# auto_resetter.net
KiCad netlist of a schematic drawn in EAGLE
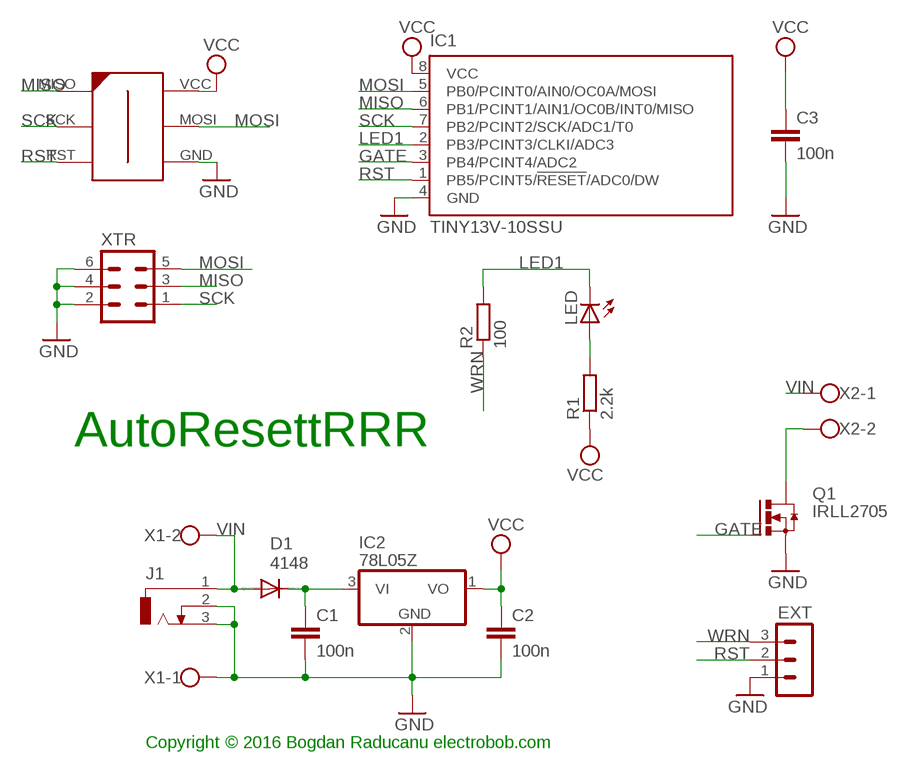
[diagram p0: schematic, sheet 1]

(export (version "E")
  (design (tool "Eeschema 10.0.6"))
  (components
    (comp (ref "C1")
      (value "100n")
      (footprint "eagle-import:C0805")
      (libsource (lib "eagle-import") (part "C-EUC0805"))
    )
    (comp (ref "C2")
      (value "100n")
      (footprint "eagle-import:C0805")
      (libsource (lib "eagle-import") (part "C-EUC0805"))
    )
    (comp (ref "C3")
      (value "100n")
      (footprint "eagle-import:C0805")
      (libsource (lib "eagle-import") (part "C-EUC0805"))
    )
    (comp (ref "D1")
      (value "4148")
      (footprint "eagle-import:MINIMELF")
      (libsource (lib "eagle-import") (part "DIODE-MINIMELF"))
    )
    (comp (ref "EXT")
      (value "MA03-1")
      (footprint "eagle-import:MA03-1")
      (libsource (lib "eagle-import") (part "MA03-1"))
    )
    (comp (ref "IC1")
      (value "TINY13V-10SSU")
      (footprint "eagle-import:8S1")
      (fields (field (name "MPN") "ATTINY13V-10SSU"))
      (libsource (lib "eagle-import") (part "TINY13SSUV-10"))
    )
    (comp (ref "IC2")
      (value "78L05Z")
      (footprint "eagle-import:TO92")
      (libsource (lib "eagle-import") (part "78ZL05"))
    )
    (comp (ref "J1")
      (value "DCJ0303")
      (footprint "eagle-import:DCJ0303")
      (libsource (lib "eagle-import") (part "DCJ0303"))
    )
    (comp (ref "LED")
      (value "LED3MM")
      (footprint "eagle-import:LED3MM")
      (libsource (lib "eagle-import") (part "LED3MM"))
    )
    (comp (ref "Q1")
      (value "IRLL2705")
      (footprint "eagle-import:SOT223")
      (libsource (lib "eagle-import") (part "N-HEXFET-2D_?-SOT232"))
    )
    (comp (ref "R1")
      (value "2.2k")
      (footprint "eagle-import:M0805")
      (libsource (lib "eagle-import") (part "R-EU_M0805"))
    )
    (comp (ref "R2")
      (value "100")
      (footprint "eagle-import:M0805")
      (libsource (lib "eagle-import") (part "R-EU_M0805"))
    )
    (comp (ref "U$1")
      (value "AVR-ISP-6-EDGE")
      (footprint "eagle-import:6PAD_ISP")
      (libsource (lib "eagle-import") (part "AVR-ISP-6-EDGE"))
    )
    (comp (ref "X1")
      (value "W237-102")
      (footprint "eagle-import:W237-102")
      (fields (field (name "MPN") "237-102"))
      (libsource (lib "eagle-import") (part "W237-102"))
    )
    (comp (ref "X2")
      (value "W237-102")
      (footprint "eagle-import:W237-102")
      (fields (field (name "MPN") "237-102"))
      (libsource (lib "eagle-import") (part "W237-102"))
    )
    (comp (ref "XTR")
      (value "MA03-2")
      (footprint "eagle-import:MA03-2")
      (libsource (lib "eagle-import") (part "MA03-2"))
    )
  )
  (nets
    (net (code "1") (name "/GATE") (class "Default")
      (node (ref "IC1") (pin "3") (pinfunction "PB4/PCINT4/ADC2_3") (pintype "bidirectional"))
      (node (ref "Q1") (pin "1") (pinfunction "G_1") (pintype "passive"))
    )
    (net (code "2") (name "/LED1") (class "Default")
      (node (ref "IC1") (pin "2") (pinfunction "PB3/PCINT3/CLKI/ADC3_2") (pintype "bidirectional"))
      (node (ref "LED") (pin "K") (pinfunction "C_K") (pintype "passive"))
      (node (ref "R2") (pin "2") (pinfunction "2_2") (pintype "passive"))
    )
    (net (code "3") (name "/MISO") (class "Default")
      (node (ref "IC1") (pin "6") (pinfunction "PB1/PCINT1/AIN1/OC0B/INT0/MISO_6") (pintype "bidirectional"))
      (node (ref "U$1") (pin "MISO") (pinfunction "P$1_MISO") (pintype "bidirectional"))
      (node (ref "XTR") (pin "3") (pinfunction "3_3") (pintype "passive"))
    )
    (net (code "4") (name "/MOSI") (class "Default")
      (node (ref "IC1") (pin "5") (pinfunction "PB0/PCINT0/AIN0/OC0A/MOSI_5") (pintype "bidirectional"))
      (node (ref "U$1") (pin "MOSI") (pinfunction "P$5_MOSI") (pintype "bidirectional"))
      (node (ref "XTR") (pin "5") (pinfunction "5_5") (pintype "passive"))
    )
    (net (code "5") (name "/RST") (class "Default")
      (node (ref "EXT") (pin "2") (pinfunction "2_2") (pintype "passive"))
      (node (ref "IC1") (pin "1") (pinfunction "PB5/PCINT5/~{RESET}/ADC0/DW_1") (pintype "bidirectional"))
      (node (ref "U$1") (pin "RST") (pinfunction "P$3_RST") (pintype "bidirectional"))
    )
    (net (code "6") (name "/SCK") (class "Default")
      (node (ref "IC1") (pin "7") (pinfunction "PB2/PCINT2/SCK/ADC1/T0_7") (pintype "bidirectional"))
      (node (ref "U$1") (pin "SCK") (pinfunction "P$2_SCK") (pintype "bidirectional"))
      (node (ref "XTR") (pin "1") (pinfunction "1_1") (pintype "passive"))
    )
    (net (code "7") (name "/VIN") (class "Default")
      (node (ref "D1") (pin "A") (pinfunction "A_A") (pintype "passive"))
      (node (ref "J1") (pin "1") (pinfunction "1_1") (pintype "passive"))
      (node (ref "X1") (pin "2") (pinfunction "KL_2") (pintype "passive"))
      (node (ref "X2") (pin "1") (pinfunction "KL_1") (pintype "passive"))
    )
    (net (code "8") (name "/WRN") (class "Default")
      (node (ref "EXT") (pin "3") (pinfunction "3_3") (pintype "passive"))
      (node (ref "R2") (pin "1") (pinfunction "1_1") (pintype "passive"))
    )
    (net (code "9") (name "GND") (class "Default")
      (node (ref "C1") (pin "2") (pinfunction "2_2") (pintype "passive"))
      (node (ref "C2") (pin "2") (pinfunction "2_2") (pintype "passive"))
      (node (ref "C3") (pin "2") (pinfunction "2_2") (pintype "passive"))
      (node (ref "EXT") (pin "1") (pinfunction "1_1") (pintype "passive"))
      (node (ref "IC1") (pin "4") (pinfunction "GND_4") (pintype "power_in"))
      (node (ref "IC2") (pin "2") (pinfunction "GND_2") (pintype "passive"))
      (node (ref "J1") (pin "2") (pinfunction "2_2") (pintype "passive"))
      (node (ref "J1") (pin "3") (pinfunction "3_3") (pintype "passive"))
      (node (ref "Q1") (pin "3") (pinfunction "S_3") (pintype "passive"))
      (node (ref "U$1") (pin "GND") (pinfunction "P$4_GND") (pintype "bidirectional"))
      (node (ref "X1") (pin "1") (pinfunction "KL_1") (pintype "passive"))
      (node (ref "XTR") (pin "2") (pinfunction "2_2") (pintype "passive"))
      (node (ref "XTR") (pin "4") (pinfunction "4_4") (pintype "passive"))
      (node (ref "XTR") (pin "6") (pinfunction "6_6") (pintype "passive"))
    )
    (net (code "10") (name "Net-(IC2-VI)") (class "Default")
      (node (ref "C1") (pin "1") (pinfunction "1_1") (pintype "passive"))
      (node (ref "D1") (pin "C") (pinfunction "C_C") (pintype "passive"))
      (node (ref "IC2") (pin "3") (pinfunction "VI_3") (pintype "input"))
    )
    (net (code "11") (name "Net-(LED-PadA)") (class "Default")
      (node (ref "LED") (pin "A") (pinfunction "A_A") (pintype "passive"))
      (node (ref "R1") (pin "2") (pinfunction "2_2") (pintype "passive"))
    )
    (net (code "12") (name "Net-(X2B-KL)") (class "Default")
      (node (ref "Q1") (pin "2") (pinfunction "D_2") (pintype "passive"))
      (node (ref "Q1") (pin "4") (pinfunction "D_4") (pintype "passive"))
      (node (ref "X2") (pin "2") (pinfunction "KL_2") (pintype "passive"))
    )
    (net (code "13") (name "VCC") (class "Default")
      (node (ref "C2") (pin "1") (pinfunction "1_1") (pintype "passive"))
      (node (ref "C3") (pin "1") (pinfunction "1_1") (pintype "passive"))
      (node (ref "IC1") (pin "8") (pinfunction "VCC_8") (pintype "power_in"))
      (node (ref "IC2") (pin "1") (pinfunction "VO_1") (pintype "passive"))
      (node (ref "R1") (pin "1") (pinfunction "1_1") (pintype "passive"))
      (node (ref "U$1") (pin "VCC") (pinfunction "P$6_VCC") (pintype "bidirectional"))
    )
  )
)
